# 12_USB_HUB.net
KiCad netlist of a schematic drawn in Altium Designer
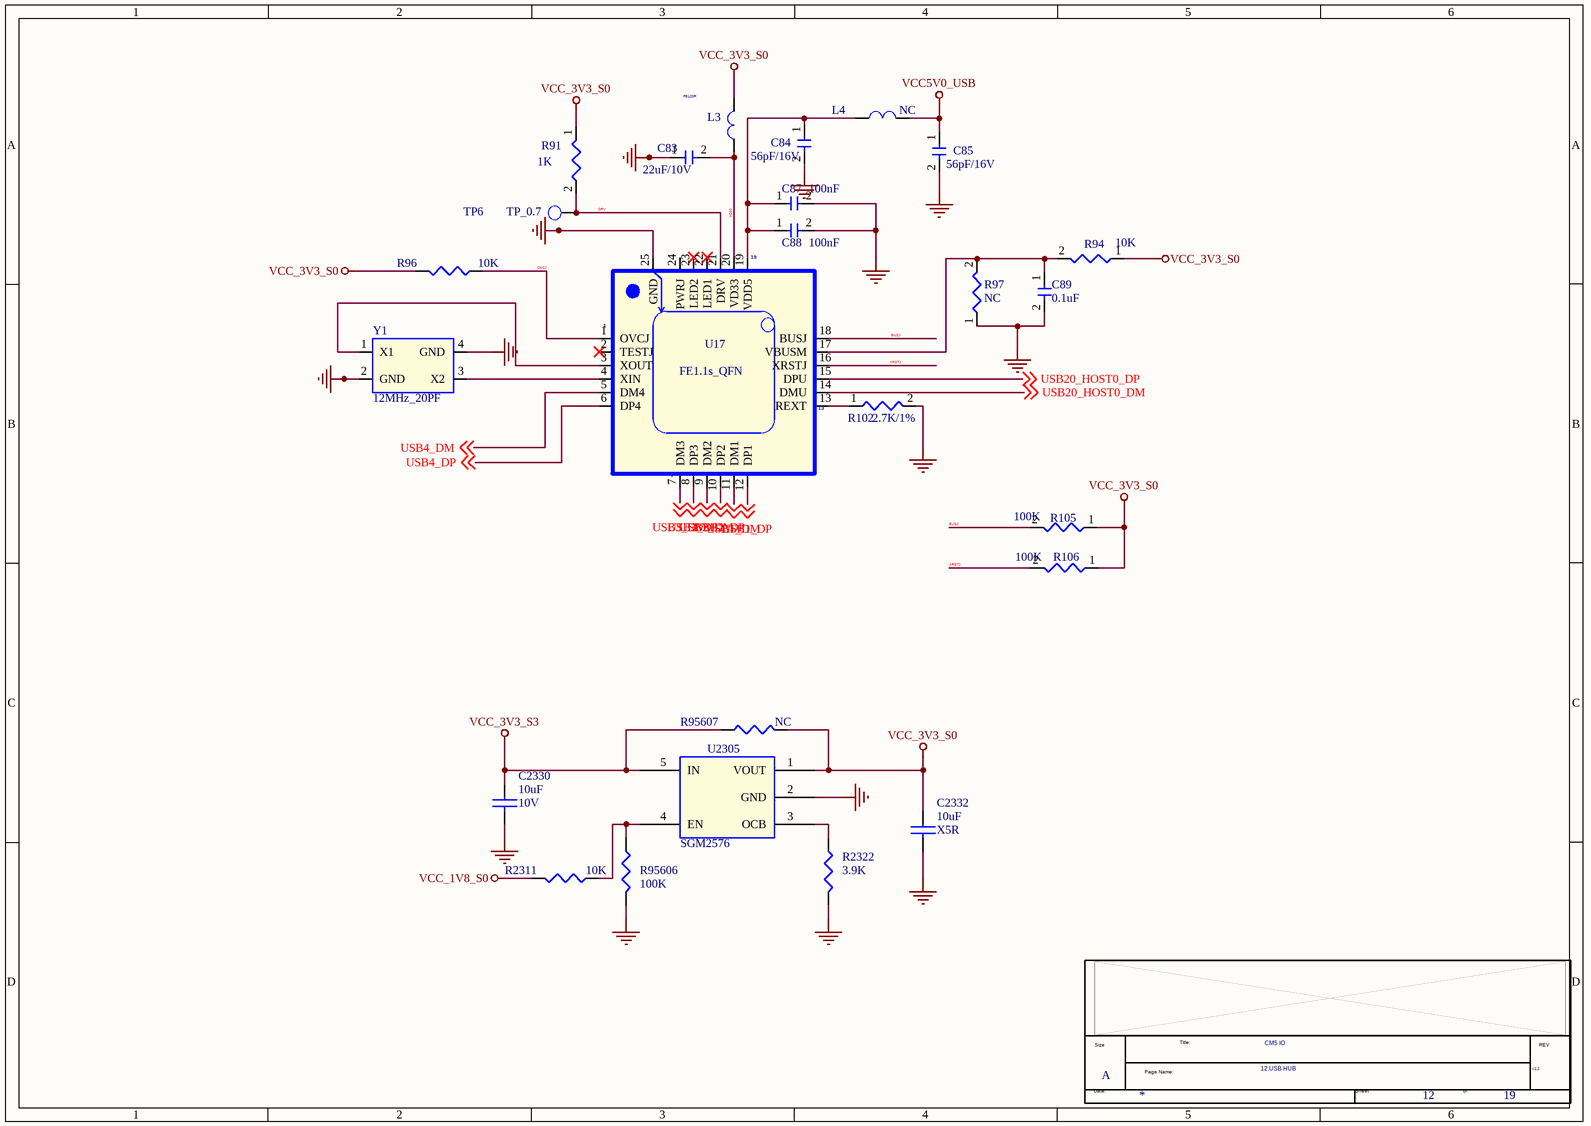
[diagram p0: 12_USB_HUB.SchDoc]

(export (version "E")
  (design (tool "Eeschema 10.0.6"))
  (components
    (comp (ref "*")
      (value "radxa_1010")
      (fields
        (field (name "DOC") "12.USB HUB")
        (field (name "REVCODE") "V2.2")
        (field (name "TITLE") "CM5 IO")
        (field (name "PAGE SIZE") "A")
        (field (name "PAGE NUMBER") "12")
        (field (name "PAGE COUNT") "19")
      )
      (libsource (lib "*") (part "radxa_1010"))
    )
    (comp (ref "C83") (value "22uF/10V") (footprint "C0603") (libsource (lib "*") (part "CAP_0.1uF_0603")))
    (comp (ref "C84") (value "56pF/16V") (footprint "C0603") (libsource (lib "*") (part "CAP_0.1uF_0603")))
    (comp (ref "C85") (value "56pF/16V") (footprint "C0603") (libsource (lib "*") (part "CAP_0.1uF_0603")))
    (comp (ref "C87") (value "100nF") (footprint "C0603") (libsource (lib "*") (part "CAP_0.1uF_0603")))
    (comp (ref "C88") (value "100nF") (footprint "C0603") (libsource (lib "*") (part "CAP_0.1uF_0603")))
    (comp (ref "C89") (value "0.1uF") (footprint "C0603") (libsource (lib "*") (part "CAP_0.1uF_0603")))
    (comp (ref "C2330")
      (value "10uF")
      (footprint "C0603")
      (description "cap,10.00uF,+/-10%,10V,X5R,C0603")
      (fields
        (field (name "VOLTAGE") "10V")
        (field (name "MANUFACTURER") "TDK")
        (field (name "TOLERANCE") "10%")
        (field (name "CREATED BY") "JJJ")
      )
      (libsource (lib "*") (part "CAP NP_0_Dup2"))
    )
    (comp (ref "C2332")
      (value "10uF")
      (footprint "C0603")
      (description "cap,10.00uF,+/-10%,10V,X5R,C0603")
      (fields
        (field (name "VOLTAGE") "10V")
        (field (name "DIELECTRIC") "X5R")
        (field (name "TOLERANCE") "10%")
        (field (name "CREATED BY") "JJJ")
      )
      (libsource (lib "*") (part "CAP NP_0_Dup2"))
    )
    (comp (ref "L3") (value "FB120R") (footprint "R0402") (libsource (lib "*") (part "CHOKE RF")))
    (comp (ref "L4") (value "NC") (footprint "L0402") (libsource (lib "") (part "CHOKE RF_1")))
    (comp (ref "R91") (value "1K") (footprint "R0603") (libsource (lib "*") (part "RES_0603")))
    (comp (ref "R94") (value "10K") (footprint "R0603") (libsource (lib "*") (part "RES_0603")))
    (comp (ref "R96")
      (value "10K")
      (footprint "R0402")
      (description "通用厚膜电阻,0R,+/-5%,R0402,1/16W.")
      (fields
        (field (name "TOLERANCE") "5%")
        (field (name "MANUFACTURER") "YAGEO")
        (field (name "CREATED BY") "YTL")
      )
      (libsource (lib "*") (part "RESISTOR_0_Dup3"))
    )
    (comp (ref "R97") (value "NC") (footprint "R0603") (libsource (lib "*") (part "RES_0603")))
    (comp (ref "R102") (value "2.7K/1%") (footprint "R0603") (libsource (lib "*") (part "RES_0603")))
    (comp (ref "R105") (value "100K") (footprint "R0603") (libsource (lib "*") (part "RES_0603")))
    (comp (ref "R106") (value "100K") (footprint "R0603") (libsource (lib "*") (part "RES_0603")))
    (comp (ref "R2311")
      (value "10K")
      (footprint "R0402")
      (description "通用厚膜电阻,10K,+/-5%,R0402,1/16W.")
      (fields
        (field (name "TOLERANCE") "5%")
        (field (name "MANUFACTURER") "YAGEO")
        (field (name "CREATED BY") "YTL")
      )
      (libsource (lib "*") (part "RESISTOR_1_Dup1"))
    )
    (comp (ref "R2322")
      (value "3.9K")
      (footprint "R0402")
      (description "通用厚膜电阻,4K7,+/-5%,R0402,1/16W.")
      (fields
        (field (name "TOLERANCE") "5%")
        (field (name "MANUFACTURER") "YAGEO")
        (field (name "CREATED BY") "YTL")
      )
      (libsource (lib "*") (part "RESISTOR_1_Dup1"))
    )
    (comp (ref "R95606")
      (value "100K")
      (footprint "R0402")
      (description "通用厚膜电阻,10K,+/-5%,R0402,1/16W.")
      (fields
        (field (name "TOLERANCE") "5%")
        (field (name "MANUFACTURER") "YAGEO")
        (field (name "CREATED BY") "YTL")
      )
      (libsource (lib "*") (part "RESISTOR_1_Dup1"))
    )
    (comp (ref "R95607")
      (value "NC")
      (footprint "R0402")
      (description "通用厚膜电阻,4K7,+/-5%,R0402,1/16W.")
      (fields
        (field (name "TOLERANCE") "5%")
        (field (name "MANUFACTURER") "YAGEO")
        (field (name "CREATED BY") "YTL")
      )
      (libsource (lib "*") (part "RESISTOR_1_Dup1"))
    )
    (comp (ref "TP6")
      (value "TP_0.7")
      (footprint "TEST")
      (description "Test Point 0.7mm")
      (fields (field (name "CREATED BY") "JJJ"))
      (libsource (lib "*") (part "TP"))
    )
    (comp (ref "U17")
      (value "FE1.1s_QFN")
      (footprint "QFN24")
      (libsource (lib "*") (part "FE1_1s_B_QFN24_2"))
    )
    (comp (ref "U2305")
      (value "SGM2576")
      (footprint "SOT_23_5")
      (description "1A Current Limited Load Switch")
      (fields (field (name "MANUFACTURER") "Torch-chip（汤诚电子）") (field (name "CREATED BY") "JJJ"))
      (libsource (lib "*") (part "SWITCH_SY6280"))
    )
    (comp (ref "Y1")
      (value "12MHz_20PF")
      (footprint "CRY-3225")
      (description "无源晶振，25M，3225,±10ppm，10pF，Hosonic")
      (fields (field (name "MANUFACTURER") "Hosonic(鸿星电子)") (field (name "CREATED BY") "JJJ"))
      (libsource (lib "*") (part "CRYSTAL_4P"))
    )
  )
  (nets
    (net (code "1") (name "/BUSJ") (class "Default")
      (node (ref "R105") (pin "2") (pinfunction "2_2") (pintype "passive"))
      (node (ref "U17") (pin "18") (pinfunction "BUSJ_18") (pintype "passive"))
    )
    (net (code "2") (name "/DRV") (class "Default")
      (node (ref "R91") (pin "2") (pinfunction "2_2") (pintype "passive"))
      (node (ref "TP6") (pin "1") (pinfunction "1_1") (pintype "passive"))
      (node (ref "U17") (pin "21") (pinfunction "DRV_21") (pintype "passive"))
    )
    (net (code "3") (name "/OVCJ") (class "Default")
      (node (ref "R96") (pin "2") (pinfunction "2_2") (pintype "passive"))
      (node (ref "U17") (pin "1") (pinfunction "OVCJ_1") (pintype "passive"))
    )
    (net (code "4") (name "/VD33") (class "Default")
      (node (ref "C83") (pin "2") (pinfunction "2_2") (pintype "passive"))
      (node (ref "L3") (pin "1") (pinfunction "1_1") (pintype "passive"))
      (node (ref "U17") (pin "20") (pinfunction "VD33_20") (pintype "passive"))
    )
    (net (code "5") (name "/XRSTJ") (class "Default")
      (node (ref "R106") (pin "2") (pinfunction "2_2") (pintype "passive"))
      (node (ref "U17") (pin "16") (pinfunction "XRSTJ_16") (pintype "passive"))
    )
    (net (code "6") (name "GND") (class "Default")
      (node (ref "C2330") (pin "2") (pinfunction "2_2") (pintype "passive"))
      (node (ref "C2332") (pin "2") (pinfunction "2_2") (pintype "passive"))
      (node (ref "C83") (pin "1") (pinfunction "1_1") (pintype "passive"))
      (node (ref "C84") (pin "2") (pinfunction "2_2") (pintype "passive"))
      (node (ref "C85") (pin "2") (pinfunction "2_2") (pintype "passive"))
      (node (ref "C87") (pin "2") (pinfunction "2_2") (pintype "passive"))
      (node (ref "C88") (pin "2") (pinfunction "2_2") (pintype "passive"))
      (node (ref "C89") (pin "2") (pinfunction "2_2") (pintype "passive"))
      (node (ref "R102") (pin "2") (pinfunction "2_2") (pintype "passive"))
      (node (ref "R2322") (pin "2") (pinfunction "2_2") (pintype "passive"))
      (node (ref "R95606") (pin "1") (pinfunction "1_1") (pintype "passive"))
      (node (ref "R97") (pin "1") (pinfunction "1_1") (pintype "passive"))
      (node (ref "U17") (pin "25") (pinfunction "GND_25") (pintype "power_in"))
      (node (ref "U2305") (pin "2") (pinfunction "GND_2") (pintype "passive"))
      (node (ref "Y1") (pin "2") (pinfunction "GND_2") (pintype "power_in"))
      (node (ref "Y1") (pin "4") (pinfunction "GND_4") (pintype "power_in"))
    )
    (net (code "7") (name "Net-(U17-REXT)") (class "Default")
      (node (ref "R102") (pin "1") (pinfunction "1_1") (pintype "passive"))
      (node (ref "U17") (pin "13") (pinfunction "REXT_13") (pintype "passive"))
    )
    (net (code "8") (name "Net-(U17-VBUSM)") (class "Default")
      (node (ref "C89") (pin "1") (pinfunction "1_1") (pintype "passive"))
      (node (ref "R94") (pin "2") (pinfunction "2_2") (pintype "passive"))
      (node (ref "R97") (pin "2") (pinfunction "2_2") (pintype "passive"))
      (node (ref "U17") (pin "17") (pinfunction "VBUSM_17") (pintype "passive"))
    )
    (net (code "9") (name "Net-(U17-VDD5)") (class "Default")
      (node (ref "C84") (pin "1") (pinfunction "1_1") (pintype "passive"))
      (node (ref "C87") (pin "1") (pinfunction "1_1") (pintype "passive"))
      (node (ref "C88") (pin "1") (pinfunction "1_1") (pintype "passive"))
      (node (ref "L4") (pin "2") (pinfunction "2_2") (pintype "passive"))
      (node (ref "U17") (pin "19") (pinfunction "VDD5_19") (pintype "passive"))
    )
    (net (code "10") (name "Net-(U17-XIN)") (class "Default")
      (node (ref "U17") (pin "4") (pinfunction "XIN_4") (pintype "passive"))
      (node (ref "Y1") (pin "3") (pinfunction "X2_3") (pintype "passive"))
    )
    (net (code "11") (name "Net-(U17-XOUT)") (class "Default")
      (node (ref "U17") (pin "3") (pinfunction "XOUT_3") (pintype "passive"))
      (node (ref "Y1") (pin "1") (pinfunction "X1_1") (pintype "passive"))
    )
    (net (code "12") (name "Net-(U2305-EN)") (class "Default")
      (node (ref "R2311") (pin "2") (pinfunction "2_2") (pintype "passive"))
      (node (ref "R95606") (pin "2") (pinfunction "2_2") (pintype "passive"))
      (node (ref "U2305") (pin "4") (pinfunction "EN_4") (pintype "passive"))
    )
    (net (code "13") (name "Net-(U2305-OCB)") (class "Default")
      (node (ref "R2322") (pin "1") (pinfunction "1_1") (pintype "passive"))
      (node (ref "U2305") (pin "3") (pinfunction "OCB_3") (pintype "passive"))
    )
    (net (code "14") (name "USB1_DM") (class "Default")
      (node (ref "U17") (pin "11") (pinfunction "DM1_11") (pintype "passive"))
    )
    (net (code "15") (name "USB1_DP") (class "Default")
      (node (ref "U17") (pin "12") (pinfunction "DP1_12") (pintype "passive"))
    )
    (net (code "16") (name "USB2_DM") (class "Default")
      (node (ref "U17") (pin "9") (pinfunction "DM2_9") (pintype "passive"))
    )
    (net (code "17") (name "USB2_DP") (class "Default")
      (node (ref "U17") (pin "10") (pinfunction "DP2_10") (pintype "passive"))
    )
    (net (code "18") (name "USB3_DM") (class "Default")
      (node (ref "U17") (pin "7") (pinfunction "DM3_7") (pintype "passive"))
    )
    (net (code "19") (name "USB3_DP") (class "Default")
      (node (ref "U17") (pin "8") (pinfunction "DP3_8") (pintype "passive"))
    )
    (net (code "20") (name "USB4_DM") (class "Default")
      (node (ref "U17") (pin "5") (pinfunction "DM4_5") (pintype "passive"))
    )
    (net (code "21") (name "USB4_DP") (class "Default")
      (node (ref "U17") (pin "6") (pinfunction "DP4_6") (pintype "passive"))
    )
    (net (code "22") (name "USB20_HOST0_DM") (class "Default")
      (node (ref "U17") (pin "14") (pinfunction "DMU_14") (pintype "passive"))
    )
    (net (code "23") (name "USB20_HOST0_DP") (class "Default")
      (node (ref "U17") (pin "15") (pinfunction "DPU_15") (pintype "passive"))
    )
    (net (code "24") (name "VCC5V0_USB") (class "Default")
      (node (ref "C85") (pin "1") (pinfunction "1_1") (pintype "passive"))
      (node (ref "L4") (pin "1") (pinfunction "1_1") (pintype "passive"))
    )
    (net (code "25") (name "VCC_1V8_S0") (class "Default")
      (node (ref "R2311") (pin "1") (pinfunction "1_1") (pintype "passive"))
    )
    (net (code "26") (name "VCC_3V3_S0") (class "Default")
      (node (ref "C2332") (pin "1") (pinfunction "1_1") (pintype "passive"))
      (node (ref "L3") (pin "2") (pinfunction "2_2") (pintype "passive"))
      (node (ref "R105") (pin "1") (pinfunction "1_1") (pintype "passive"))
      (node (ref "R106") (pin "1") (pinfunction "1_1") (pintype "passive"))
      (node (ref "R91") (pin "1") (pinfunction "1_1") (pintype "passive"))
      (node (ref "R94") (pin "1") (pinfunction "1_1") (pintype "passive"))
      (node (ref "R95607") (pin "2") (pinfunction "2_2") (pintype "passive"))
      (node (ref "R96") (pin "1") (pinfunction "1_1") (pintype "passive"))
      (node (ref "U2305") (pin "1") (pinfunction "VOUT_1") (pintype "passive"))
    )
    (net (code "27") (name "VCC_3V3_S3") (class "Default")
      (node (ref "C2330") (pin "1") (pinfunction "1_1") (pintype "passive"))
      (node (ref "R95607") (pin "1") (pinfunction "1_1") (pintype "passive"))
      (node (ref "U2305") (pin "5") (pinfunction "IN_5") (pintype "passive"))
    )
    (net (code "28") (name "unconnected-(U17-LED1-Pad22)") (class "Default")
      (node (ref "U17") (pin "22") (pinfunction "LED1_22") (pintype "passive+no_connect"))
    )
    (net (code "29") (name "unconnected-(U17-LED2-Pad23)") (class "Default")
      (node (ref "U17") (pin "23") (pinfunction "LED2_23") (pintype "passive+no_connect"))
    )
    (net (code "30") (name "unconnected-(U17-PWRJ-Pad24)") (class "Default")
      (node (ref "U17") (pin "24") (pinfunction "PWRJ_24") (pintype "passive"))
    )
    (net (code "31") (name "unconnected-(U17-TESTJ-Pad2)") (class "Default")
      (node (ref "U17") (pin "2") (pinfunction "TESTJ_2") (pintype "passive+no_connect"))
    )
  )
)
